# xplorer.net
KiCad netlist of a schematic drawn in EAGLE
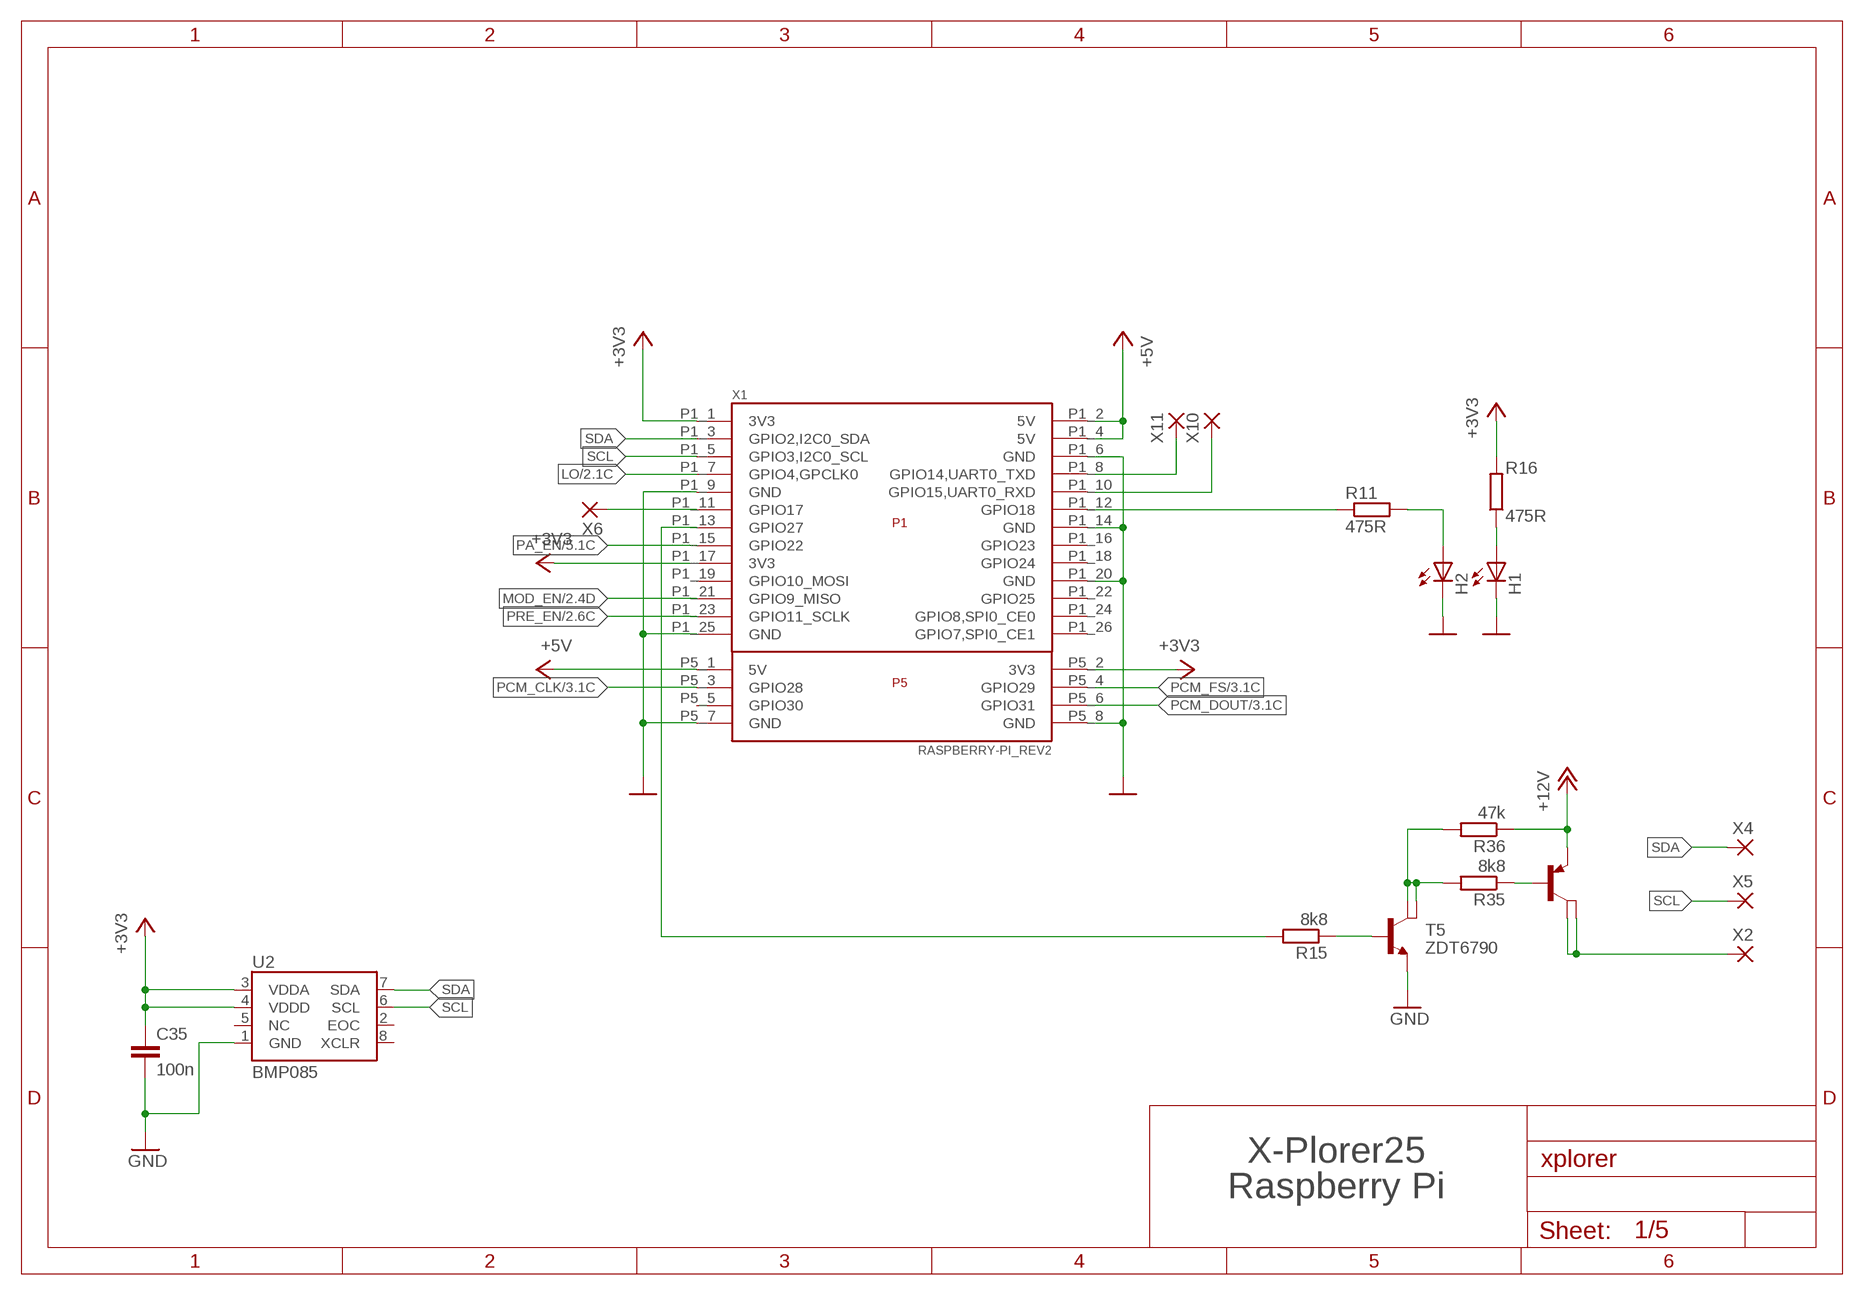
[diagram p0: schematic, sheet 1]
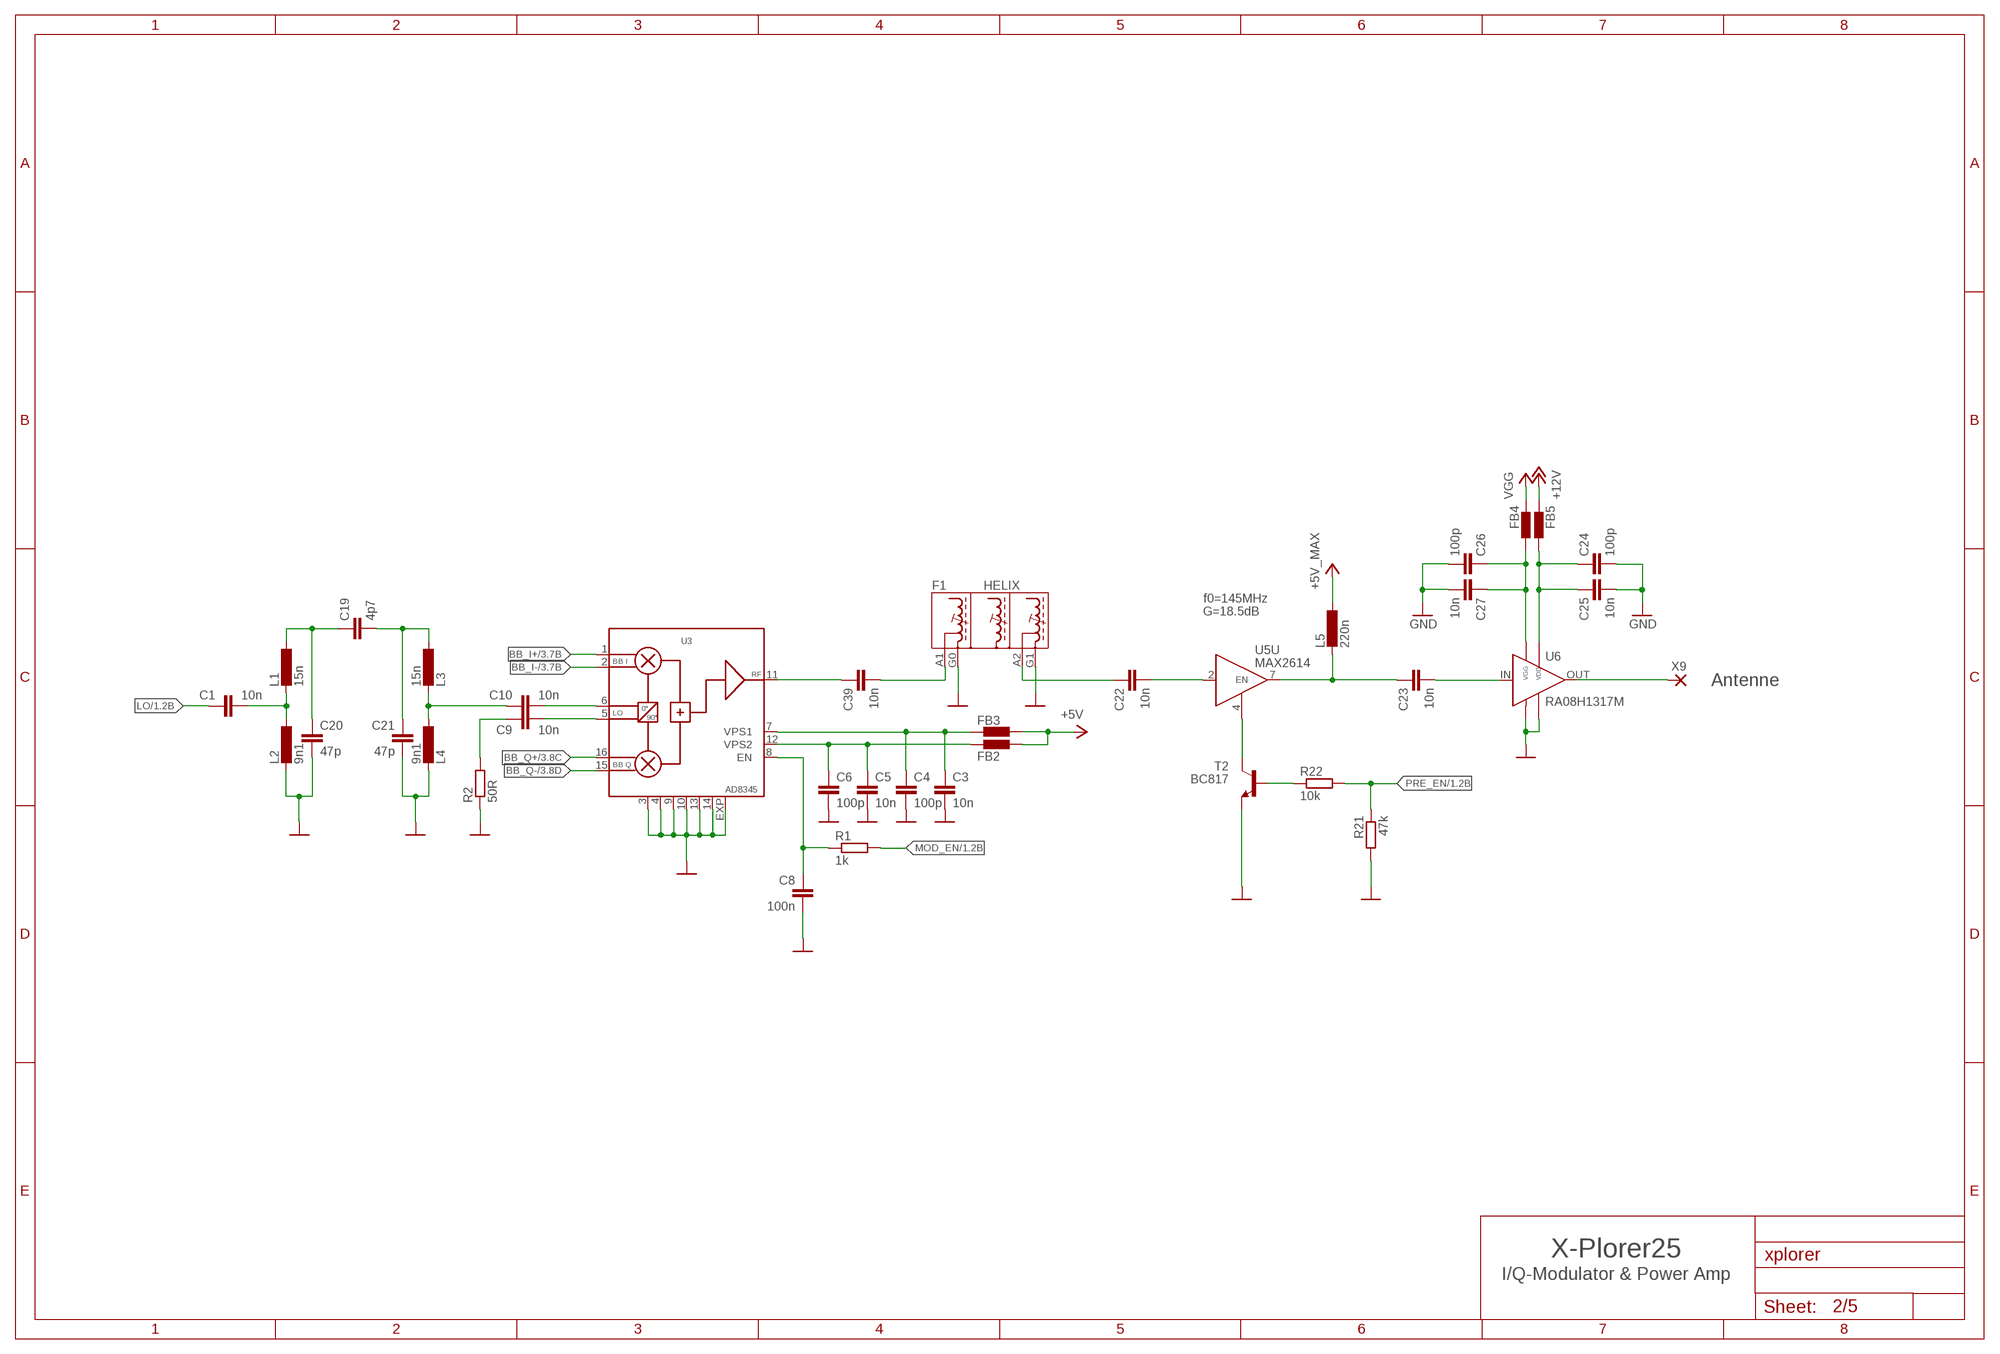
[diagram p1: schematic, sheet 2]
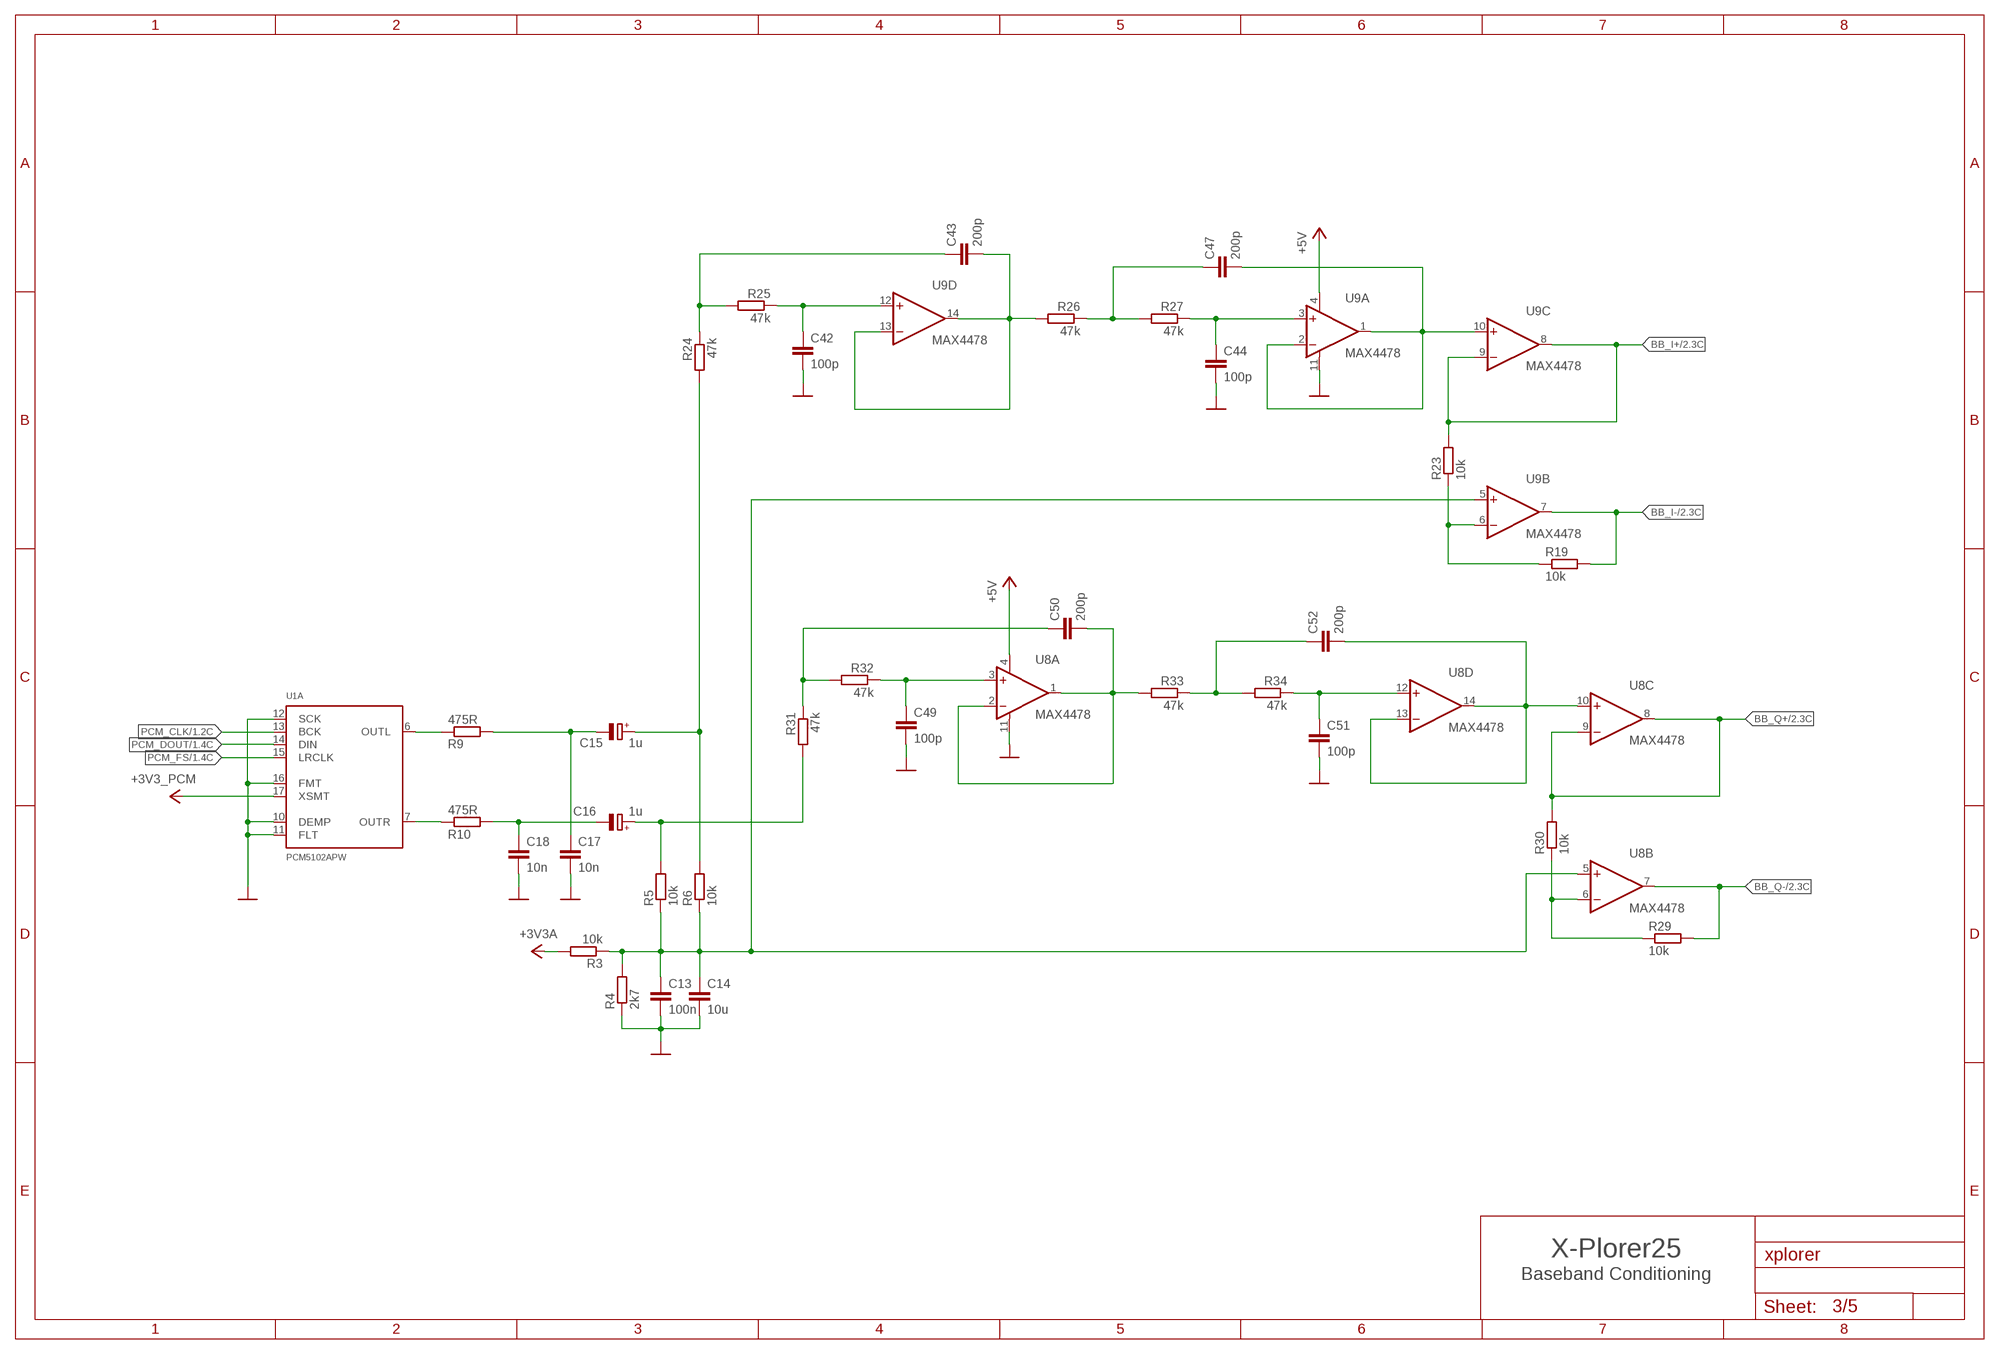
[diagram p2: schematic, sheet 3]
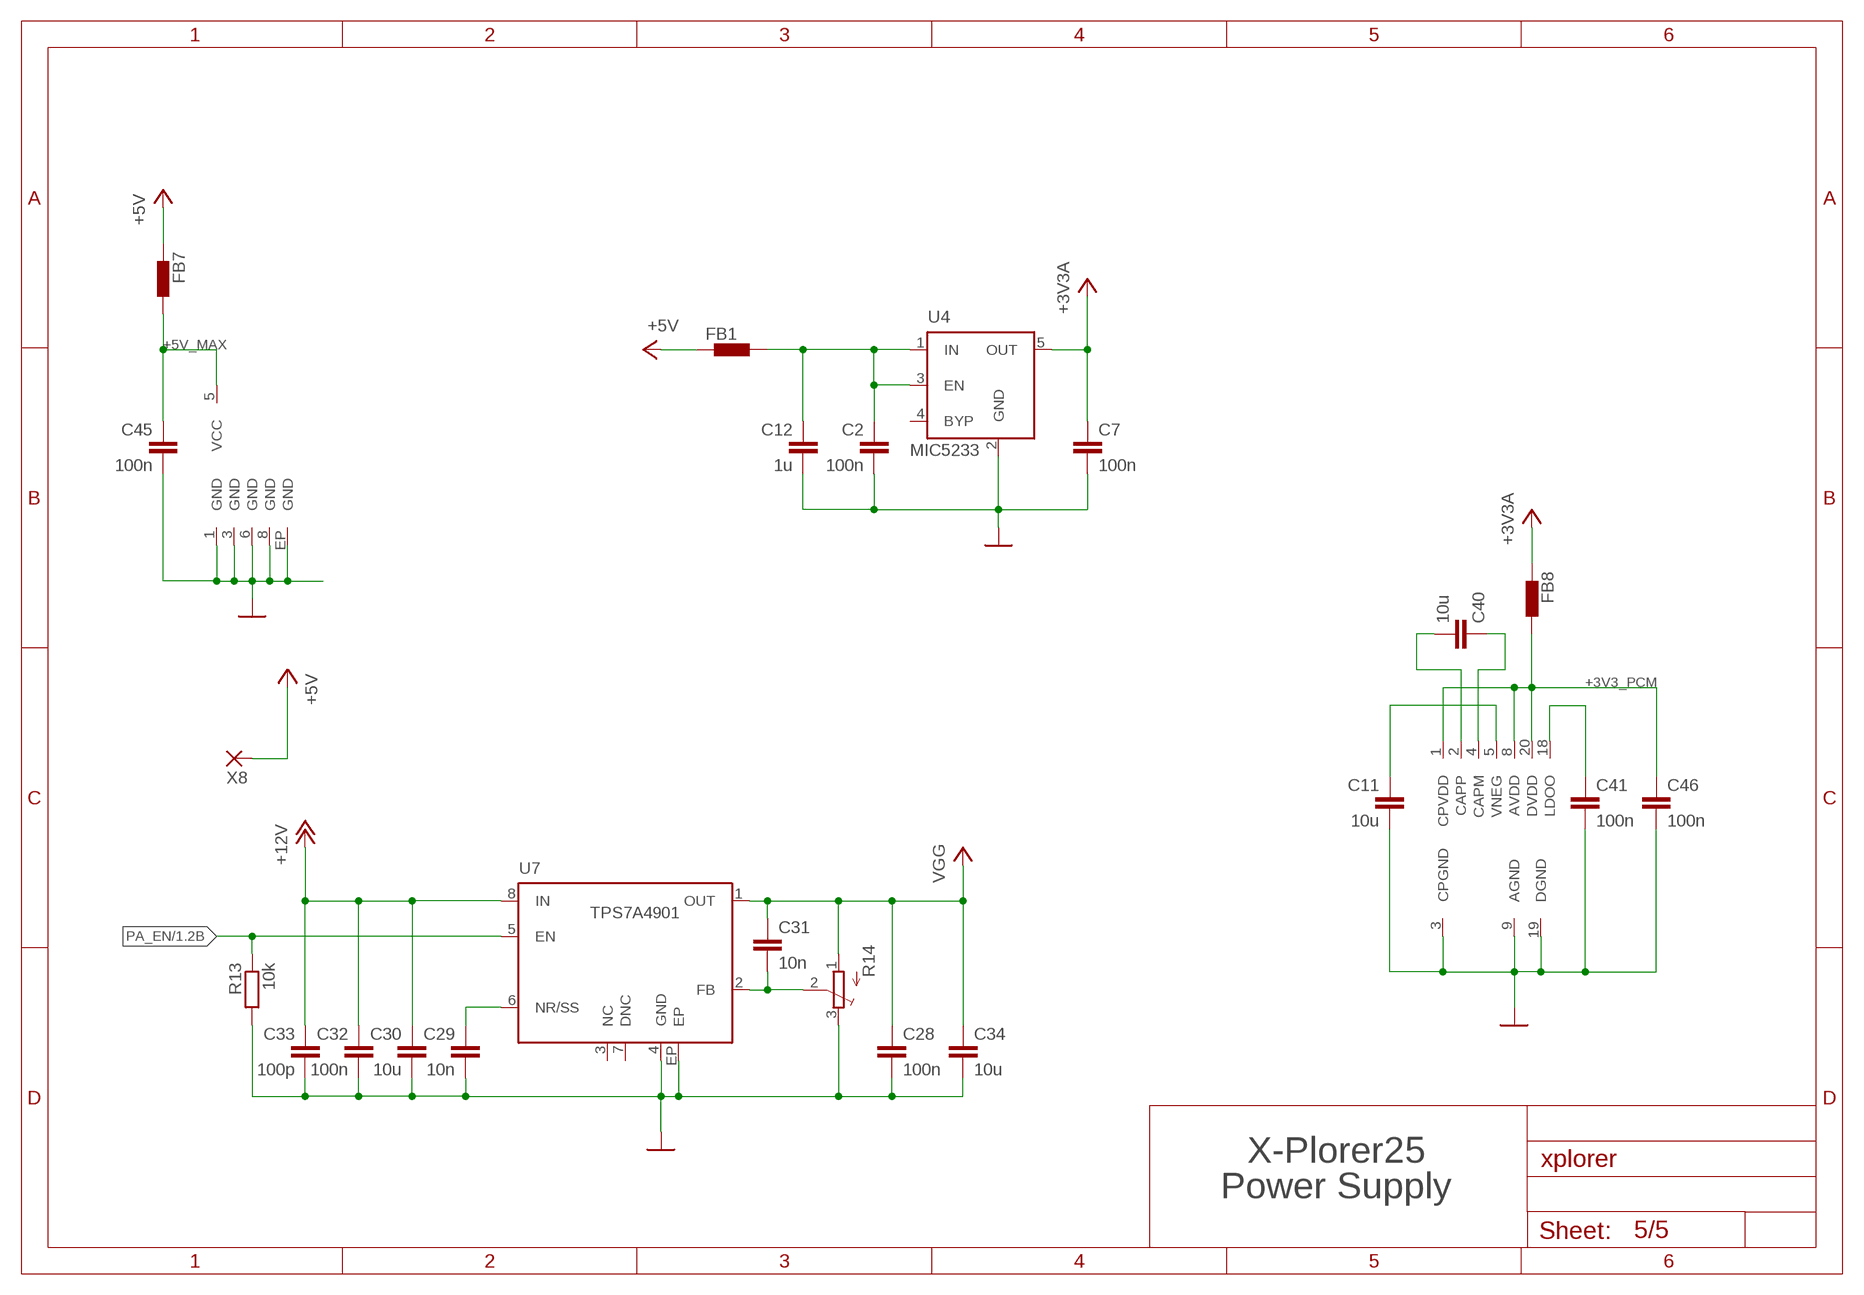
[diagram p3: schematic, sheet 5]

(export (version "E")
  (design (tool "Eeschema 10.0.6"))
  (components
    (comp (ref "C1")
      (value "10n")
      (footprint "eagle-import:C0603")
      (libsource (lib "eagle-import") (part "C-EUC0603"))
    )
    (comp (ref "C3")
      (value "10n")
      (footprint "eagle-import:C0603")
      (libsource (lib "eagle-import") (part "C-EUC0603"))
    )
    (comp (ref "C4")
      (value "100p")
      (footprint "eagle-import:C0603")
      (libsource (lib "eagle-import") (part "C-EUC0603"))
    )
    (comp (ref "C5")
      (value "10n")
      (footprint "eagle-import:C0603")
      (libsource (lib "eagle-import") (part "C-EUC0603"))
    )
    (comp (ref "C6")
      (value "100p")
      (footprint "eagle-import:C0603")
      (libsource (lib "eagle-import") (part "C-EUC0603"))
    )
    (comp (ref "C8")
      (value "100n")
      (footprint "eagle-import:C0603")
      (libsource (lib "eagle-import") (part "C-EUC0603"))
    )
    (comp (ref "C9")
      (value "10n")
      (footprint "eagle-import:C0603")
      (libsource (lib "eagle-import") (part "C-EUC0603"))
    )
    (comp (ref "C10")
      (value "10n")
      (footprint "eagle-import:C0603")
      (libsource (lib "eagle-import") (part "C-EUC0603"))
    )
    (comp (ref "C19")
      (value "4p7")
      (footprint "eagle-import:C0603")
      (libsource (lib "eagle-import") (part "C-EUC0603"))
    )
    (comp (ref "C20")
      (value "47p")
      (footprint "eagle-import:C1812")
      (libsource (lib "eagle-import") (part "C-EUC1812"))
    )
    (comp (ref "C21")
      (value "47p")
      (footprint "eagle-import:C1812")
      (libsource (lib "eagle-import") (part "C-EUC1812"))
    )
    (comp (ref "C22")
      (value "10n")
      (footprint "eagle-import:C0603")
      (libsource (lib "eagle-import") (part "C-EUC0603"))
    )
    (comp (ref "C23")
      (value "10n")
      (footprint "eagle-import:C0603")
      (libsource (lib "eagle-import") (part "C-EUC0603"))
    )
    (comp (ref "C24")
      (value "100p")
      (footprint "eagle-import:C0603")
      (libsource (lib "eagle-import") (part "C-EUC0603"))
    )
    (comp (ref "C25")
      (value "10n")
      (footprint "eagle-import:C0603")
      (libsource (lib "eagle-import") (part "C-EUC0603"))
    )
    (comp (ref "C26")
      (value "100p")
      (footprint "eagle-import:C0603")
      (libsource (lib "eagle-import") (part "C-EUC0603"))
    )
    (comp (ref "C27")
      (value "10n")
      (footprint "eagle-import:C0603")
      (libsource (lib "eagle-import") (part "C-EUC0603"))
    )
    (comp (ref "C39")
      (value "10n")
      (footprint "eagle-import:C0603")
      (libsource (lib "eagle-import") (part "C-EUC0603"))
    )
    (comp (ref "F1")
      (value "HELIX")
      (footprint "eagle-import:CBT13")
      (libsource (lib "eagle-import") (part "HELIX"))
    )
    (comp (ref "FB2")
      (value "BML15H")
      (footprint "eagle-import:R0603")
      (libsource (lib "eagle-import") (part "BML15H"))
    )
    (comp (ref "FB3")
      (value "BML15H")
      (footprint "eagle-import:R0603")
      (libsource (lib "eagle-import") (part "BML15H"))
    )
    (comp (ref "FB4")
      (value "BML15H")
      (footprint "eagle-import:R0603")
      (libsource (lib "eagle-import") (part "BML15H"))
    )
    (comp (ref "FB5")
      (value "BML15H")
      (footprint "eagle-import:R0603")
      (libsource (lib "eagle-import") (part "BML15H"))
    )
    (comp (ref "L1")
      (value "15n")
      (footprint "eagle-import:L2012C")
      (libsource (lib "eagle-import") (part "L-EUL2012C"))
    )
    (comp (ref "L2")
      (value "9n1")
      (footprint "eagle-import:L2012C")
      (libsource (lib "eagle-import") (part "L-EUL2012C"))
    )
    (comp (ref "L3")
      (value "15n")
      (footprint "eagle-import:L2012C")
      (libsource (lib "eagle-import") (part "L-EUL2012C"))
    )
    (comp (ref "L4")
      (value "9n1")
      (footprint "eagle-import:L2012C")
      (libsource (lib "eagle-import") (part "L-EUL2012C"))
    )
    (comp (ref "L5")
      (value "220n")
      (footprint "eagle-import:L2012C")
      (libsource (lib "eagle-import") (part "L-EUL2012C"))
    )
    (comp (ref "R1")
      (value "1k")
      (footprint "eagle-import:R0603")
      (libsource (lib "eagle-import") (part "R-EU_R0603"))
    )
    (comp (ref "R2")
      (value "50R")
      (footprint "eagle-import:R0603")
      (libsource (lib "eagle-import") (part "R-EU_R0603"))
    )
    (comp (ref "R21")
      (value "47k")
      (footprint "eagle-import:R0603")
      (libsource (lib "eagle-import") (part "R-EU_R0603"))
    )
    (comp (ref "R22")
      (value "10k")
      (footprint "eagle-import:R0603")
      (libsource (lib "eagle-import") (part "R-EU_R0603"))
    )
    (comp (ref "T2")
      (value "BC817")
      (footprint "eagle-import:SOT23-BEC")
      (libsource (lib "eagle-import") (part "BC817SMD-16LT1"))
    )
    (comp (ref "U3")
      (value "AD8345")
      (footprint "eagle-import:TSSOP16EXP")
      (libsource (lib "eagle-import") (part "AD8345"))
    )
    (comp (ref "U5")
      (value "MAX2614")
      (footprint "eagle-import:TDFN8-2X3MM")
      (libsource (lib "eagle-import") (part "MAX2615"))
    )
    (comp (ref "U6")
      (value "RA08H1317M")
      (footprint "eagle-import:RA08H1317M")
      (libsource (lib "eagle-import") (part "RA08H1317M"))
    )
    (comp (ref "X9")
      (value "SMD2")
      (footprint "eagle-import:SMD1,27-2,54")
      (libsource (lib "eagle-import") (part "SMD2"))
    )
    (comp (ref "C13")
      (value "100n")
      (footprint "eagle-import:C0603")
      (libsource (lib "eagle-import") (part "C-EUC0603"))
    )
    (comp (ref "C14")
      (value "10u")
      (footprint "eagle-import:C0603")
      (libsource (lib "eagle-import") (part "C-EUC0603"))
    )
    (comp (ref "C15")
      (value "1u")
      (footprint "eagle-import:CT3528")
      (libsource (lib "eagle-import") (part "CPOL-EUCT3528"))
    )
    (comp (ref "C16")
      (value "1u")
      (footprint "eagle-import:CT3528")
      (libsource (lib "eagle-import") (part "CPOL-EUCT3528"))
    )
    (comp (ref "C17")
      (value "10n")
      (footprint "eagle-import:C0603")
      (libsource (lib "eagle-import") (part "C-EUC0603"))
    )
    (comp (ref "C18")
      (value "10n")
      (footprint "eagle-import:C0603")
      (libsource (lib "eagle-import") (part "C-EUC0603"))
    )
    (comp (ref "C42")
      (value "100p")
      (footprint "eagle-import:C0603")
      (libsource (lib "eagle-import") (part "C-EUC0603"))
    )
    (comp (ref "C43")
      (value "200p")
      (footprint "eagle-import:C0805")
      (libsource (lib "eagle-import") (part "C-EUC0805"))
    )
    (comp (ref "C44")
      (value "100p")
      (footprint "eagle-import:C0603")
      (libsource (lib "eagle-import") (part "C-EUC0603"))
    )
    (comp (ref "C47")
      (value "200p")
      (footprint "eagle-import:C0805")
      (libsource (lib "eagle-import") (part "C-EUC0805"))
    )
    (comp (ref "C49")
      (value "100p")
      (footprint "eagle-import:C0603")
      (libsource (lib "eagle-import") (part "C-EUC0603"))
    )
    (comp (ref "C50")
      (value "200p")
      (footprint "eagle-import:C0805")
      (libsource (lib "eagle-import") (part "C-EUC0805"))
    )
    (comp (ref "C51")
      (value "100p")
      (footprint "eagle-import:C0603")
      (libsource (lib "eagle-import") (part "C-EUC0603"))
    )
    (comp (ref "C52")
      (value "200p")
      (footprint "eagle-import:C0805")
      (libsource (lib "eagle-import") (part "C-EUC0805"))
    )
    (comp (ref "R3")
      (value "10k")
      (footprint "eagle-import:R0603")
      (libsource (lib "eagle-import") (part "R-EU_R0603"))
    )
    (comp (ref "R4")
      (value "2k7")
      (footprint "eagle-import:R0603")
      (libsource (lib "eagle-import") (part "R-EU_R0603"))
    )
    (comp (ref "R5")
      (value "10k")
      (footprint "eagle-import:R0603")
      (libsource (lib "eagle-import") (part "R-EU_R0603"))
    )
    (comp (ref "R6")
      (value "10k")
      (footprint "eagle-import:R0603")
      (libsource (lib "eagle-import") (part "R-EU_R0603"))
    )
    (comp (ref "R9")
      (value "475R")
      (footprint "eagle-import:R0603")
      (libsource (lib "eagle-import") (part "R-EU_R0603"))
    )
    (comp (ref "R10")
      (value "475R")
      (footprint "eagle-import:R0603")
      (libsource (lib "eagle-import") (part "R-EU_R0603"))
    )
    (comp (ref "R19")
      (value "10k")
      (footprint "eagle-import:R0603")
      (libsource (lib "eagle-import") (part "R-EU_R0603"))
    )
    (comp (ref "R23")
      (value "10k")
      (footprint "eagle-import:R0603")
      (libsource (lib "eagle-import") (part "R-EU_R0603"))
    )
    (comp (ref "R24")
      (value "47k")
      (footprint "eagle-import:R0603")
      (libsource (lib "eagle-import") (part "R-EU_R0603"))
    )
    (comp (ref "R25")
      (value "47k")
      (footprint "eagle-import:R0603")
      (libsource (lib "eagle-import") (part "R-EU_R0603"))
    )
    (comp (ref "R26")
      (value "47k")
      (footprint "eagle-import:R0603")
      (libsource (lib "eagle-import") (part "R-EU_R0603"))
    )
    (comp (ref "R27")
      (value "47k")
      (footprint "eagle-import:R0603")
      (libsource (lib "eagle-import") (part "R-EU_R0603"))
    )
    (comp (ref "R29")
      (value "10k")
      (footprint "eagle-import:R0603")
      (libsource (lib "eagle-import") (part "R-EU_R0603"))
    )
    (comp (ref "R30")
      (value "10k")
      (footprint "eagle-import:R0603")
      (libsource (lib "eagle-import") (part "R-EU_R0603"))
    )
    (comp (ref "R31")
      (value "47k")
      (footprint "eagle-import:R0603")
      (libsource (lib "eagle-import") (part "R-EU_R0603"))
    )
    (comp (ref "R32")
      (value "47k")
      (footprint "eagle-import:R0603")
      (libsource (lib "eagle-import") (part "R-EU_R0603"))
    )
    (comp (ref "R33")
      (value "47k")
      (footprint "eagle-import:R0603")
      (libsource (lib "eagle-import") (part "R-EU_R0603"))
    )
    (comp (ref "R34")
      (value "47k")
      (footprint "eagle-import:R0603")
      (libsource (lib "eagle-import") (part "R-EU_R0603"))
    )
    (comp (ref "U1")
      (value "PCM5102APW")
      (footprint "eagle-import:PW_R-PDSO-G20")
      (libsource (lib "eagle-import") (part "PCM5102APW"))
    )
    (comp (ref "U8")
      (value "MAX4478")
      (footprint "eagle-import:SO14")
      (fields
        (field (name "MF") "TEXAS INSTRUMENTS")
        (field (name "MPN") "OPA4132UA")
        (field (name "MF_1") "TEXAS INSTRUMENTS")
        (field (name "MPN_1") "OPA4132UA")
        (field (name "OC_FARNELL") "1212302")
        (field (name "OC_NEWARK") "80K6028")
      )
      (libsource (lib "eagle-import") (part "OPA4132U"))
    )
    (comp (ref "U9")
      (value "MAX4478")
      (footprint "eagle-import:SO14")
      (fields (field (name "MF") "TEXAS INSTRUMENTS") (field (name "MPN") "OPA4132UA"))
      (libsource (lib "eagle-import") (part "OPA4132U"))
    )
    (comp (ref "C2")
      (value "100n")
      (footprint "eagle-import:C0603")
      (libsource (lib "eagle-import") (part "C-EUC0603"))
    )
    (comp (ref "C7")
      (value "100n")
      (footprint "eagle-import:C0603")
      (libsource (lib "eagle-import") (part "C-EUC0603"))
    )
    (comp (ref "C11")
      (value "10u")
      (footprint "eagle-import:C0603")
      (libsource (lib "eagle-import") (part "C-EUC0603"))
    )
    (comp (ref "C12")
      (value "1u")
      (footprint "eagle-import:C0603")
      (libsource (lib "eagle-import") (part "C-EUC0603"))
    )
    (comp (ref "C28")
      (value "100n")
      (footprint "eagle-import:C0603")
      (libsource (lib "eagle-import") (part "C-EUC0603"))
    )
    (comp (ref "C29")
      (value "10n")
      (footprint "eagle-import:C0603K")
      (libsource (lib "eagle-import") (part "C-EUC0603K"))
    )
    (comp (ref "C30")
      (value "10u")
      (footprint "eagle-import:C0805")
      (libsource (lib "eagle-import") (part "C-EUC0805"))
    )
    (comp (ref "C31")
      (value "10n")
      (footprint "eagle-import:C0603")
      (libsource (lib "eagle-import") (part "C-EUC0603"))
    )
    (comp (ref "C32")
      (value "100n")
      (footprint "eagle-import:C0603")
      (libsource (lib "eagle-import") (part "C-EUC0603"))
    )
    (comp (ref "C33")
      (value "100p")
      (footprint "eagle-import:C0603")
      (libsource (lib "eagle-import") (part "C-EUC0603"))
    )
    (comp (ref "C34")
      (value "10u")
      (footprint "eagle-import:C0805")
      (libsource (lib "eagle-import") (part "C-EUC0805"))
    )
    (comp (ref "C40")
      (value "10u")
      (footprint "eagle-import:C0603")
      (libsource (lib "eagle-import") (part "C-EUC0603"))
    )
    (comp (ref "C41")
      (value "100n")
      (footprint "eagle-import:C0603")
      (libsource (lib "eagle-import") (part "C-EUC0603"))
    )
    (comp (ref "C45")
      (value "100n")
      (footprint "eagle-import:C0603")
      (libsource (lib "eagle-import") (part "C-EUC0603"))
    )
    (comp (ref "C46")
      (value "100n")
      (footprint "eagle-import:C0603")
      (libsource (lib "eagle-import") (part "C-EUC0603"))
    )
    (comp (ref "FB1")
      (value "BML15H")
      (footprint "eagle-import:R0603")
      (libsource (lib "eagle-import") (part "BML15H"))
    )
    (comp (ref "FB7")
      (value "BML15H")
      (footprint "eagle-import:R0603")
      (libsource (lib "eagle-import") (part "BML15H"))
    )
    (comp (ref "FB8")
      (value "BML15H")
      (footprint "eagle-import:R0603")
      (libsource (lib "eagle-import") (part "BML15H"))
    )
    (comp (ref "R13")
      (value "10k")
      (footprint "eagle-import:R0603")
      (libsource (lib "eagle-import") (part "R-EU_R0603"))
    )
    (comp (ref "R14")
      (value "TRIM_EU-SM-42/43X")
      (footprint "eagle-import:SM-42_43X")
      (libsource (lib "eagle-import") (part "TRIM_EU-SM-42/43X"))
    )
    (comp (ref "U4")
      (value "MIC5233")
      (footprint "eagle-import:SOT23-5")
      (libsource (lib "eagle-import") (part "MIC5219XX"))
    )
    (comp (ref "U7")
      (value "TPS7A4901")
      (footprint "eagle-import:PW_R-PDSO-G08")
      (libsource (lib "eagle-import") (part "TPS7A4901"))
    )
    (comp (ref "X8")
      (value "SMD2")
      (footprint "eagle-import:SMD1,27-2,54")
      (libsource (lib "eagle-import") (part "SMD2"))
    )
    (comp (ref "C35")
      (value "100n")
      (footprint "eagle-import:0603")
      (libsource (lib "eagle-import") (part "C-0603"))
    )
    (comp (ref "H1")
      (value "LEDCHIPLED_0603")
      (footprint "eagle-import:CHIPLED_0603")
      (libsource (lib "eagle-import") (part "LEDCHIPLED_0603"))
    )
    (comp (ref "H2")
      (value "LEDCHIPLED_0603")
      (footprint "eagle-import:CHIPLED_0603")
      (libsource (lib "eagle-import") (part "LEDCHIPLED_0603"))
    )
    (comp (ref "R11")
      (value "475R")
      (footprint "eagle-import:R0402")
      (libsource (lib "eagle-import") (part "R-EU_R0402"))
    )
    (comp (ref "R15")
      (value "8k8")
      (footprint "eagle-import:R0603")
      (libsource (lib "eagle-import") (part "R-EU_R0603"))
    )
    (comp (ref "R16")
      (value "475R")
      (footprint "eagle-import:R0402")
      (libsource (lib "eagle-import") (part "R-EU_R0402"))
    )
    (comp (ref "R35")
      (value "8k8")
      (footprint "eagle-import:R0603")
      (libsource (lib "eagle-import") (part "R-EU_R0603"))
    )
    (comp (ref "R36")
      (value "47k")
      (footprint "eagle-import:R0603")
      (libsource (lib "eagle-import") (part "R-EU_R0603"))
    )
    (comp (ref "T5")
      (value "ZDT6790")
      (footprint "eagle-import:SOT223-8")
      (libsource (lib "eagle-import") (part "ZDT6790"))
    )
    (comp (ref "U2")
      (value "BMP085")
      (footprint "eagle-import:BMP085")
      (libsource (lib "eagle-import") (part "BMP085"))
    )
    (comp (ref "X1")
      (value "RASPBERRY-PI_REV2")
      (footprint "eagle-import:RASPBERRY-PI_REV2")
      (libsource (lib "eagle-import") (part "RASPBERRY-PI_REV2"))
    )
    (comp (ref "X2")
      (value "SMD2")
      (footprint "eagle-import:SMD1,27-2,54")
      (libsource (lib "eagle-import") (part "SMD2"))
    )
    (comp (ref "X4")
      (value "SMD2")
      (footprint "eagle-import:SMD1,27-2,54")
      (libsource (lib "eagle-import") (part "SMD2"))
    )
    (comp (ref "X5")
      (value "SMD2")
      (footprint "eagle-import:SMD1,27-2,54")
      (libsource (lib "eagle-import") (part "SMD2"))
    )
    (comp (ref "X6")
      (value "SMD2")
      (footprint "eagle-import:SMD1,27-2,54")
      (libsource (lib "eagle-import") (part "SMD2"))
    )
    (comp (ref "X10")
      (value "SMD2")
      (footprint "eagle-import:SMD1,27-2,54")
      (libsource (lib "eagle-import") (part "SMD2"))
    )
    (comp (ref "X11")
      (value "SMD2")
      (footprint "eagle-import:SMD1,27-2,54")
      (libsource (lib "eagle-import") (part "SMD2"))
    )
  )
  (nets
    (net (code "1") (name "+3V3") (class "Default")
      (node (ref "C35") (pin "1") (pinfunction "1_1") (pintype "passive"))
      (node (ref "R16") (pin "2") (pinfunction "2_2") (pintype "passive"))
      (node (ref "U2") (pin "3") (pinfunction "VDDA_3") (pintype "power_in"))
      (node (ref "U2") (pin "4") (pinfunction "VDDD_4") (pintype "power_in"))
      (node (ref "X1") (pin "P1_1") (pinfunction "3V3_P1_1") (pintype "bidirectional"))
      (node (ref "X1") (pin "P1_17") (pinfunction "3V3_P1_17") (pintype "bidirectional"))
      (node (ref "X1") (pin "P5_2") (pinfunction "3V3_P5_2") (pintype "bidirectional"))
    )
    (net (code "2") (name "+3V3A") (class "Default")
      (node (ref "C7") (pin "1") (pinfunction "1_1") (pintype "passive"))
      (node (ref "FB8") (pin "1") (pinfunction "1_1") (pintype "passive"))
      (node (ref "R3") (pin "2") (pinfunction "2_2") (pintype "passive"))
      (node (ref "U4") (pin "5") (pinfunction "OUT_5") (pintype "output"))
    )
    (net (code "3") (name "+3V3_PCM") (class "Default")
      (node (ref "C46") (pin "1") (pinfunction "1_1") (pintype "passive"))
      (node (ref "FB8") (pin "2") (pinfunction "2_2") (pintype "passive"))
      (node (ref "U1") (pin "1") (pinfunction "CPVDD_1") (pintype "power_in"))
      (node (ref "U1") (pin "17") (pinfunction "XSMT_17") (pintype "input"))
      (node (ref "U1") (pin "20") (pinfunction "DVDD_20") (pintype "power_in"))
      (node (ref "U1") (pin "8") (pinfunction "AVDD_8") (pintype "power_in"))
    )
    (net (code "4") (name "+5V") (class "Default")
      (node (ref "FB1") (pin "1") (pinfunction "1_1") (pintype "passive"))
      (node (ref "FB2") (pin "2") (pinfunction "2_2") (pintype "passive"))
      (node (ref "FB3") (pin "2") (pinfunction "2_2") (pintype "passive"))
      (node (ref "FB7") (pin "1") (pinfunction "1_1") (pintype "passive"))
      (node (ref "U8") (pin "4") (pinfunction "V+_4") (pintype "power_in"))
      (node (ref "U9") (pin "4") (pinfunction "V+_4") (pintype "power_in"))
      (node (ref "X1") (pin "P1_2") (pinfunction "5V_P1_2") (pintype "bidirectional"))
      (node (ref "X1") (pin "P1_4") (pinfunction "5V_P1_4") (pintype "bidirectional"))
      (node (ref "X1") (pin "P5_1") (pinfunction "5V_P5_1") (pintype "bidirectional"))
      (node (ref "X8") (pin "1") (pinfunction "P_1") (pintype "passive"))
    )
    (net (code "5") (name "+5V_MAX") (class "Default")
      (node (ref "C45") (pin "1") (pinfunction "1_1") (pintype "passive"))
      (node (ref "FB7") (pin "2") (pinfunction "2_2") (pintype "passive"))
      (node (ref "L5") (pin "1") (pinfunction "1_1") (pintype "passive"))
      (node (ref "U5") (pin "5") (pinfunction "VCC_5") (pintype "power_in"))
    )
    (net (code "6") (name "+12V") (class "Default")
      (node (ref "C30") (pin "1") (pinfunction "1_1") (pintype "passive"))
      (node (ref "C32") (pin "1") (pinfunction "1_1") (pintype "passive"))
      (node (ref "C33") (pin "1") (pinfunction "1_1") (pintype "passive"))
      (node (ref "FB5") (pin "1") (pinfunction "1_1") (pintype "passive"))
      (node (ref "R36") (pin "1") (pinfunction "1_1") (pintype "passive"))
      (node (ref "T5") (pin "5") (pinfunction "E_5") (pintype "passive"))
      (node (ref "U7") (pin "8") (pinfunction "IN_8") (pintype "input"))
    )
    (net (code "7") (name "BB_I+") (class "Default")
      (node (ref "R23") (pin "2") (pinfunction "2_2") (pintype "passive"))
      (node (ref "U3") (pin "1") (pinfunction "BB_I_1") (pintype "input"))
      (node (ref "U9") (pin "8") (pinfunction "OUT_8") (pintype "output"))
      (node (ref "U9") (pin "9") (pinfunction "-IN_9") (pintype "input"))
    )
    (net (code "8") (name "BB_I-") (class "Default")
      (node (ref "R19") (pin "2") (pinfunction "2_2") (pintype "passive"))
      (node (ref "U3") (pin "2") (pinfunction "~{BB_I}_2") (pintype "input"))
      (node (ref "U9") (pin "7") (pinfunction "OUT_7") (pintype "output"))
    )
    (net (code "9") (name "BB_Q+") (class "Default")
      (node (ref "R30") (pin "2") (pinfunction "2_2") (pintype "passive"))
      (node (ref "U3") (pin "16") (pinfunction "BB_Q_16") (pintype "input"))
      (node (ref "U8") (pin "8") (pinfunction "OUT_8") (pintype "output"))
      (node (ref "U8") (pin "9") (pinfunction "-IN_9") (pintype "input"))
    )
    (net (code "10") (name "BB_Q-") (class "Default")
      (node (ref "R29") (pin "2") (pinfunction "2_2") (pintype "passive"))
      (node (ref "U3") (pin "15") (pinfunction "~{BB_Q}_15") (pintype "input"))
      (node (ref "U8") (pin "7") (pinfunction "OUT_7") (pintype "output"))
    )
    (net (code "11") (name "GND") (class "Default")
      (node (ref "C11") (pin "2") (pinfunction "2_2") (pintype "passive"))
      (node (ref "C12") (pin "2") (pinfunction "2_2") (pintype "passive"))
      (node (ref "C13") (pin "2") (pinfunction "2_2") (pintype "passive"))
      (node (ref "C14") (pin "2") (pinfunction "2_2") (pintype "passive"))
      (node (ref "C17") (pin "2") (pinfunction "2_2") (pintype "passive"))
      (node (ref "C18") (pin "2") (pinfunction "2_2") (pintype "passive"))
      (node (ref "C2") (pin "2") (pinfunction "2_2") (pintype "passive"))
      (node (ref "C20") (pin "2") (pinfunction "2_2") (pintype "passive"))
      (node (ref "C21") (pin "2") (pinfunction "2_2") (pintype "passive"))
      (node (ref "C24") (pin "2") (pinfunction "2_2") (pintype "passive"))
      (node (ref "C25") (pin "2") (pinfunction "2_2") (pintype "passive"))
      (node (ref "C26") (pin "2") (pinfunction "2_2") (pintype "passive"))
      (node (ref "C27") (pin "2") (pinfunction "2_2") (pintype "passive"))
      (node (ref "C28") (pin "2") (pinfunction "2_2") (pintype "passive"))
      (node (ref "C29") (pin "2") (pinfunction "2_2") (pintype "passive"))
      (node (ref "C3") (pin "2") (pinfunction "2_2") (pintype "passive"))
      (node (ref "C30") (pin "2") (pinfunction "2_2") (pintype "passive"))
      (node (ref "C32") (pin "2") (pinfunction "2_2") (pintype "passive"))
      (node (ref "C33") (pin "2") (pinfunction "2_2") (pintype "passive"))
      (node (ref "C34") (pin "2") (pinfunction "2_2") (pintype "passive"))
      (node (ref "C35") (pin "2") (pinfunction "2_2") (pintype "passive"))
      (node (ref "C4") (pin "2") (pinfunction "2_2") (pintype "passive"))
      (node (ref "C41") (pin "2") (pinfunction "2_2") (pintype "passive"))
      (node (ref "C42") (pin "2") (pinfunction "2_2") (pintype "passive"))
      (node (ref "C44") (pin "2") (pinfunction "2_2") (pintype "passive"))
      (node (ref "C45") (pin "2") (pinfunction "2_2") (pintype "passive"))
      (node (ref "C46") (pin "2") (pinfunction "2_2") (pintype "passive"))
      (node (ref "C49") (pin "2") (pinfunction "2_2") (pintype "passive"))
      (node (ref "C5") (pin "2") (pinfunction "2_2") (pintype "passive"))
      (node (ref "C51") (pin "2") (pinfunction "2_2") (pintype "passive"))
      (node (ref "C6") (pin "2") (pinfunction "2_2") (pintype "passive"))
      (node (ref "C7") (pin "2") (pinfunction "2_2") (pintype "passive"))
      (node (ref "C8") (pin "2") (pinfunction "2_2") (pintype "passive"))
      (node (ref "F1") (pin "G0") (pinfunction "GND_G0") (pintype "passive"))
      (node (ref "F1") (pin "G1") (pinfunction "GND_G1") (pintype "passive"))
      (node (ref "H1") (pin "C") (pinfunction "C_C") (pintype "passive"))
      (node (ref "H2") (pin "C") (pinfunction "C_C") (pintype "passive"))
      (node (ref "L2") (pin "2") (pinfunction "2_2") (pintype "passive"))
      (node (ref "L4") (pin "2") (pinfunction "2_2") (pintype "passive"))
      (node (ref "R13") (pin "2") (pinfunction "2_2") (pintype "passive"))
      (node (ref "R14") (pin "3") (pinfunction "E_3") (pintype "passive"))
      (node (ref "R2") (pin "1") (pinfunction "1_1") (pintype "passive"))
      (node (ref "R21") (pin "2") (pinfunction "2_2") (pintype "passive"))
      (node (ref "R4") (pin "1") (pinfunction "1_1") (pintype "passive"))
      (node (ref "T2") (pin "E") (pinfunction "E_E") (pintype "passive"))
      (node (ref "T5") (pin "7") (pinfunction "E_7") (pintype "passive"))
      (node (ref "U1") (pin "10") (pinfunction "DEMP_10") (pintype "input"))
      (node (ref "U1") (pin "11") (pinfunction "FLT_11") (pintype "input"))
      (node (ref "U1") (pin "12") (pinfunction "SCK_12") (pintype "input"))
      (node (ref "U1") (pin "16") (pinfunction "FMT_16") (pintype "input"))
      (node (ref "U1") (pin "19") (pinfunction "DGND_19") (pintype "power_in"))
      (node (ref "U1") (pin "3") (pinfunction "CPGND_3") (pintype "power_in"))
      (node (ref "U1") (pin "9") (pinfunction "AGND_9") (pintype "power_in"))
      (node (ref "U2") (pin "1") (pinfunction "GND_1") (pintype "power_in"))
      (node (ref "U3") (pin "10") (pinfunction "GND_10") (pintype "power_in"))
      (node (ref "U3") (pin "13") (pinfunction "GND_13") (pintype "power_in"))
      (node (ref "U3") (pin "14") (pinfunction "GND_14") (pintype "power_in"))
      (node (ref "U3") (pin "3") (pinfunction "GND_3") (pintype "power_in"))
      (node (ref "U3") (pin "4") (pinfunction "GND_4") (pintype "power_in"))
      (node (ref "U3") (pin "9") (pinfunction "GND_9") (pintype "power_in"))
      (node (ref "U3") (pin "EXP") (pinfunction "GND_EXP") (pintype "power_in"))
      (node (ref "U4") (pin "2") (pinfunction "GND_2") (pintype "power_in"))
      (node (ref "U5") (pin "1") (pinfunction "GND_1") (pintype "power_in"))
      (node (ref "U5") (pin "3") (pinfunction "GND_3") (pintype "power_in"))
      (node (ref "U5") (pin "6") (pinfunction "GND_6") (pintype "power_in"))
      (node (ref "U5") (pin "8") (pinfunction "GND_8") (pintype "power_in"))
      (node (ref "U5") (pin "EP") (pinfunction "GND_EP") (pintype "power_in"))
      (node (ref "U6") (pin "G1") (pinfunction "GND_G1") (pintype "power_in"))
      (node (ref "U6") (pin "G2") (pinfunction "GND_G2") (pintype "power_in"))
      (node (ref "U7") (pin "4") (pinfunction "GND_4") (pintype "power_in"))
      (node (ref "U7") (pin "EP") (pinfunction "EP_EP") (pintype "passive"))
      (node (ref "U8") (pin "11") (pinfunction "V-_11") (pintype "power_in"))
      (node (ref "U9") (pin "11") (pinfunction "V-_11") (pintype "power_in"))
      (node (ref "X1") (pin "P1_14") (pinfunction "GND_P1_14") (pintype "bidirectional"))
      (node (ref "X1") (pin "P1_20") (pinfunction "GND_P1_20") (pintype "bidirectional"))
      (node (ref "X1") (pin "P1_25") (pinfunction "GND_P1_25") (pintype "bidirectional"))
      (node (ref "X1") (pin "P1_6") (pinfunction "GND_P1_6") (pintype "bidirectional"))
      (node (ref "X1") (pin "P1_9") (pinfunction "GND_P1_9") (pintype "bidirectional"))
      (node (ref "X1") (pin "P5_7") (pinfunction "GND_P5_7") (pintype "bidirectional"))
      (node (ref "X1") (pin "P5_8") (pinfunction "GND_P5_8") (pintype "bidirectional"))
    )
    (net (code "12") (name "LO") (class "Default")
      (node (ref "C1") (pin "1") (pinfunction "1_1") (pintype "passive"))
      (node (ref "X1") (pin "P1_7") (pinfunction "GPIO4,GPCLK0_P1_7") (pintype "bidirectional"))
    )
    (net (code "13") (name "MOD_EN") (class "Default")
      (node (ref "R1") (pin "2") (pinfunction "2_2") (pintype "passive"))
      (node (ref "X1") (pin "P1_21") (pinfunction "GPIO9_MISO_P1_21") (pintype "bidirectional"))
    )
    (net (code "14") (name "Net-(C1-Pad2)") (class "Default")
      (node (ref "C1") (pin "2") (pinfunction "2_2") (pintype "passive"))
      (node (ref "L1") (pin "2") (pinfunction "2_2") (pintype "passive"))
      (node (ref "L2") (pin "1") (pinfunction "1_1") (pintype "passive"))
    )
    (net (code "15") (name "Net-(C9-Pad1)") (class "Default")
      (node (ref "C9") (pin "1") (pinfunction "1_1") (pintype "passive"))
      (node (ref "R2") (pin "2") (pinfunction "2_2") (pintype "passive"))
    )
    (net (code "16") (name "Net-(C10-Pad1)") (class "Default")
      (node (ref "C10") (pin "1") (pinfunction "1_1") (pintype "passive"))
      (node (ref "L3") (pin "2") (pinfunction "2_2") (pintype "passive"))
      (node (ref "L4") (pin "1") (pinfunction "1_1") (pintype "passive"))
    )
    (net (code "17") (name "Net-(C15-Pad+)") (class "Default")
      (node (ref "C15") (pin "+") (pinfunction "+_+") (pintype "passive"))
      (node (ref "R24") (pin "2") (pinfunction "2_2") (pintype "passive"))
      (node (ref "R6") (pin "2") (pinfunction "2_2") (pintype "passive"))
    )
    (net (code "18") (name "Net-(C15-Pad-)") (class "Default")
      (node (ref "C15") (pin "-") (pinfunction "-_-") (pintype "passive"))
      (node (ref "C17") (pin "1") (pinfunction "1_1") (pintype "passive"))
      (node (ref "R9") (pin "2") (pinfunction "2_2") (pintype "passive"))
    )
    (net (code "19") (name "Net-(C16-Pad+)") (class "Default")
      (node (ref "C16") (pin "+") (pinfunction "+_+") (pintype "passive"))
      (node (ref "R31") (pin "2") (pinfunction "2_2") (pintype "passive"))
      (node (ref "R5") (pin "2") (pinfunction "2_2") (pintype "passive"))
    )
    (net (code "20") (name "Net-(C16-Pad-)") (class "Default")
      (node (ref "C16") (pin "-") (pinfunction "-_-") (pintype "passive"))
      (node (ref "C18") (pin "1") (pinfunction "1_1") (pintype "passive"))
      (node (ref "R10") (pin "2") (pinfunction "2_2") (pintype "passive"))
    )
    (net (code "21") (name "Net-(C19-Pad1)") (class "Default")
      (node (ref "C19") (pin "1") (pinfunction "1_1") (pintype "passive"))
      (node (ref "C20") (pin "1") (pinfunction "1_1") (pintype "passive"))
      (node (ref "L1") (pin "1") (pinfunction "1_1") (pintype "passive"))
    )
    (net (code "22") (name "Net-(C19-Pad2)") (class "Default")
      (node (ref "C19") (pin "2") (pinfunction "2_2") (pintype "passive"))
      (node (ref "C21") (pin "1") (pinfunction "1_1") (pintype "passive"))
      (node (ref "L3") (pin "1") (pinfunction "1_1") (pintype "passive"))
    )
    (net (code "23") (name "Net-(C22-Pad1)") (class "Default")
      (node (ref "C22") (pin "1") (pinfunction "1_1") (pintype "passive"))
      (node (ref "F1") (pin "A2") (pinfunction "A2_A2") (pintype "passive"))
    )
    (net (code "24") (name "Net-(C23-Pad2)") (class "Default")
      (node (ref "C23") (pin "2") (pinfunction "2_2") (pintype "passive"))
      (node (ref "U6") (pin "IN") (pinfunction "IN_IN") (pintype "input"))
    )
    (net (code "25") (name "Net-(C24-Pad1)") (class "Default")
      (node (ref "C24") (pin "1") (pinfunction "1_1") (pintype "passive"))
      (node (ref "C25") (pin "1") (pinfunction "1_1") (pintype "passive"))
      (node (ref "FB5") (pin "2") (pinfunction "2_2") (pintype "passive"))
      (node (ref "U6") (pin "VDD") (pinfunction "VDD_VDD") (pintype "power_in"))
    )
    (net (code "26") (name "Net-(C26-Pad1)") (class "Default")
      (node (ref "C26") (pin "1") (pinfunction "1_1") (pintype "passive"))
      (node (ref "C27") (pin "1") (pinfunction "1_1") (pintype "passive"))
      (node (ref "FB4") (pin "2") (pinfunction "2_2") (pintype "passive"))
      (node (ref "U6") (pin "VGG") (pinfunction "VGG_VGG") (pintype "power_in"))
    )
    (net (code "27") (name "Net-(C39-Pad2)") (class "Default")
      (node (ref "C39") (pin "2") (pinfunction "2_2") (pintype "passive"))
      (node (ref "F1") (pin "A1") (pinfunction "A1_A1") (pintype "passive"))
    )
    (net (code "28") (name "Net-(C43-Pad1)") (class "Default")
      (node (ref "C43") (pin "1") (pinfunction "1_1") (pintype "passive"))
      (node (ref "R24") (pin "1") (pinfunction "1_1") (pintype "passive"))
      (node (ref "R25") (pin "2") (pinfunction "2_2") (pintype "passive"))
    )
    (net (code "29") (name "Net-(C47-Pad1)") (class "Default")
      (node (ref "C47") (pin "1") (pinfunction "1_1") (pintype "passive"))
      (node (ref "R26") (pin "1") (pinfunction "1_1") (pintype "passive"))
      (node (ref "R27") (pin "2") (pinfunction "2_2") (pintype "passive"))
    )
    (net (code "30") (name "Net-(C50-Pad1)") (class "Default")
      (node (ref "C50") (pin "1") (pinfunction "1_1") (pintype "passive"))
      (node (ref "R31") (pin "1") (pinfunction "1_1") (pintype "passive"))
      (node (ref "R32") (pin "2") (pinfunction "2_2") (pintype "passive"))
    )
    (net (code "31") (name "Net-(C52-Pad1)") (class "Default")
      (node (ref "C52") (pin "1") (pinfunction "1_1") (pintype "passive"))
      (node (ref "R33") (pin "1") (pinfunction "1_1") (pintype "passive"))
      (node (ref "R34") (pin "2") (pinfunction "2_2") (pintype "passive"))
    )
    (net (code "32") (name "Net-(H1-PadA)") (class "Default")
      (node (ref "H1") (pin "A") (pinfunction "A_A") (pintype "passive"))
      (node (ref "R16") (pin "1") (pinfunction "1_1") (pintype "passive"))
    )
    (net (code "33") (name "Net-(H2-PadA)") (class "Default")
      (node (ref "H2") (pin "A") (pinfunction "A_A") (pintype "passive"))
      (node (ref "R11") (pin "2") (pinfunction "2_2") (pintype "passive"))
    )
    (net (code "34") (name "Net-(R14-S)") (class "Default")
      (node (ref "C31") (pin "2") (pinfunction "2_2") (pintype "passive"))
      (node (ref "R14") (pin "2") (pinfunction "S_2") (pintype "passive"))
      (node (ref "U7") (pin "2") (pinfunction "FB_2") (pintype "passive"))
    )
    (net (code "35") (name "Net-(R22-Pad1)") (class "Default")
      (node (ref "R22") (pin "1") (pinfunction "1_1") (pintype "passive"))
      (node (ref "T2") (pin "B") (pinfunction "B_B") (pintype "passive"))
    )
    (net (code "36") (name "Net-(T5A-B)") (class "Default")
      (node (ref "R15") (pin "1") (pinfunction "1_1") (pintype "passive"))
      (node (ref "T5") (pin "8") (pinfunction "B_8") (pintype "passive"))
    )
    (net (code "37") (name "Net-(T5A-C1)") (class "Default")
      (node (ref "R35") (pin "2") (pinfunction "2_2") (pintype "passive"))
      (node (ref "R36") (pin "2") (pinfunction "2_2") (pintype "passive"))
      (node (ref "T5") (pin "1") (pinfunction "C1_1") (pintype "passive"))
      (node (ref "T5") (pin "2") (pinfunction "C2_2") (pintype "passive"))
    )
    (net (code "38") (name "Net-(T5B-B)") (class "Default")
      (node (ref "R35") (pin "1") (pinfunction "1_1") (pintype "passive"))
      (node (ref "T5") (pin "6") (pinfunction "B_6") (pintype "passive"))
    )
    (net (code "39") (name "Net-(T5B-C1)") (class "Default")
      (node (ref "T5") (pin "3") (pinfunction "C1_3") (pintype "passive"))
      (node (ref "T5") (pin "4") (pinfunction "C2_4") (pintype "passive"))
      (node (ref "X2") (pin "1") (pinfunction "P_1") (pintype "passive"))
    )
    (net (code "40") (name "Net-(U1A-OUTL)") (class "Default")
      (node (ref "R9") (pin "1") (pinfunction "1_1") (pintype "passive"))
      (node (ref "U1") (pin "6") (pinfunction "OUTL_6") (pintype "output"))
    )
    (net (code "41") (name "Net-(U1A-OUTR)") (class "Default")
      (node (ref "R10") (pin "1") (pinfunction "1_1") (pintype "passive"))
      (node (ref "U1") (pin "7") (pinfunction "OUTR_7") (pintype "output"))
    )
    (net (code "42") (name "Net-(U1B-CAPM)") (class "Default")
      (node (ref "C40") (pin "1") (pinfunction "1_1") (pintype "passive"))
      (node (ref "U1") (pin "4") (pinfunction "CAPM_4") (pintype "output"))
    )
    (net (code "43") (name "Net-(U1B-CAPP)") (class "Default")
      (node (ref "C40") (pin "2") (pinfunction "2_2") (pintype "passive"))
      (node (ref "U1") (pin "2") (pinfunction "CAPP_2") (pintype "output"))
    )
    (net (code "44") (name "Net-(U1B-LDOO)") (class "Default")
      (node (ref "C41") (pin "1") (pinfunction "1_1") (pintype "passive"))
      (node (ref "U1") (pin "18") (pinfunction "LDOO_18") (pintype "output"))
    )
    (net (code "45") (name "Net-(U1B-VNEG)") (class "Default")
      (node (ref "C11") (pin "1") (pinfunction "1_1") (pintype "passive"))
      (node (ref "U1") (pin "5") (pinfunction "VNEG_5") (pintype "output"))
    )
    (net (code "46") (name "Net-(U3-EN)") (class "Default")
      (node (ref "C8") (pin "1") (pinfunction "1_1") (pintype "passive"))
      (node (ref "R1") (pin "1") (pinfunction "1_1") (pintype "passive"))
      (node (ref "U3") (pin "8") (pinfunction "EN_8") (pintype "input"))
    )
    (net (code "47") (name "Net-(U3-LO)") (class "Default")
      (node (ref "C10") (pin "2") (pinfunction "2_2") (pintype "passive"))
      (node (ref "U3") (pin "6") (pinfunction "LO_6") (pintype "input"))
    )
    (net (code "48") (name "Net-(U3-RF)") (class "Default")
      (node (ref "C39") (pin "1") (pinfunction "1_1") (pintype "passive"))
      (node (ref "U3") (pin "11") (pinfunction "RF_11") (pintype "output"))
    )
    (net (code "49") (name "Net-(U3-VPS1)") (class "Default")
      (node (ref "C3") (pin "1") (pinfunction "1_1") (pintype "passive"))
      (node (ref "C4") (pin "1") (pinfunction "1_1") (pintype "passive"))
      (node (ref "FB3") (pin "1") (pinfunction "1_1") (pintype "passive"))
      (node (ref "U3") (pin "7") (pinfunction "VPS1_7") (pintype "power_in"))
    )
    (net (code "50") (name "Net-(U3-VPS2)") (class "Default")
      (node (ref "C5") (pin "1") (pinfunction "1_1") (pintype "passive"))
      (node (ref "C6") (pin "1") (pinfunction "1_1") (pintype "passive"))
      (node (ref "FB2") (pin "1") (pinfunction "1_1") (pintype "passive"))
      (node (ref "U3") (pin "12") (pinfunction "VPS2_12") (pintype "power_in"))
    )
    (net (code "51") (name "Net-(U3-~{LO})") (class "Default")
      (node (ref "C9") (pin "2") (pinfunction "2_2") (pintype "passive"))
      (node (ref "U3") (pin "5") (pinfunction "~{LO}_5") (pintype "input"))
    )
    (net (code "52") (name "Net-(U4-EN)") (class "Default")
      (node (ref "C12") (pin "1") (pinfunction "1_1") (pintype "passive"))
      (node (ref "C2") (pin "1") (pinfunction "1_1") (pintype "passive"))
      (node (ref "FB1") (pin "2") (pinfunction "2_2") (pintype "passive"))
      (node (ref "U4") (pin "1") (pinfunction "IN_1") (pintype "input"))
      (node (ref "U4") (pin "3") (pinfunction "EN_3") (pintype "input"))
    )
    (net (code "53") (name "Net-(U5B-EN)") (class "Default")
      (node (ref "T2") (pin "C") (pinfunction "C_C") (pintype "passive"))
      (node (ref "U5") (pin "4") (pinfunction "EN_4") (pintype "input"))
    )
    (net (code "54") (name "Net-(U5B-IN)") (class "Default")
      (node (ref "C22") (pin "2") (pinfunction "2_2") (pintype "passive"))
      (node (ref "U5") (pin "2") (pinfunction "IN_2") (pintype "input"))
    )
    (net (code "55") (name "Net-(U5B-OUT)") (class "Default")
      (node (ref "C23") (pin "1") (pinfunction "1_1") (pintype "passive"))
      (node (ref "L5") (pin "2") (pinfunction "2_2") (pintype "passive"))
      (node (ref "U5") (pin "7") (pinfunction "OUT_7") (pintype "output"))
    )
    (net (code "56") (name "Net-(U7-NR{slash}SS)") (class "Default")
      (node (ref "C29") (pin "1") (pinfunction "1_1") (pintype "passive"))
      (node (ref "U7") (pin "6") (pinfunction "NR/SS_6") (pintype "passive"))
    )
    (net (code "57") (name "Net-(U8A-+IN)") (class "Default")
      (node (ref "C49") (pin "1") (pinfunction "1_1") (pintype "passive"))
      (node (ref "R32") (pin "1") (pinfunction "1_1") (pintype "passive"))
      (node (ref "U8") (pin "3") (pinfunction "+IN_3") (pintype "input"))
    )
    (net (code "58") (name "Net-(U8A--IN)") (class "Default")
      (node (ref "C50") (pin "2") (pinfunction "2_2") (pintype "passive"))
      (node (ref "R33") (pin "2") (pinfunction "2_2") (pintype "passive"))
      (node (ref "U8") (pin "1") (pinfunction "OUT_1") (pintype "output"))
      (node (ref "U8") (pin "2") (pinfunction "-IN_2") (pintype "input"))
    )
    (net (code "59") (name "Net-(U8B-+IN)") (class "Default")
      (node (ref "C13") (pin "1") (pinfunction "1_1") (pintype "passive"))
      (node (ref "C14") (pin "1") (pinfunction "1_1") (pintype "passive"))
      (node (ref "R3") (pin "1") (pinfunction "1_1") (pintype "passive"))
      (node (ref "R4") (pin "2") (pinfunction "2_2") (pintype "passive"))
      (node (ref "R5") (pin "1") (pinfunction "1_1") (pintype "passive"))
      (node (ref "R6") (pin "1") (pinfunction "1_1") (pintype "passive"))
      (node (ref "U8") (pin "5") (pinfunction "+IN_5") (pintype "input"))
      (node (ref "U9") (pin "5") (pinfunction "+IN_5") (pintype "input"))
    )
    (net (code "60") (name "Net-(U8B--IN)") (class "Default")
      (node (ref "R29") (pin "1") (pinfunction "1_1") (pintype "passive"))
      (node (ref "R30") (pin "1") (pinfunction "1_1") (pintype "passive"))
      (node (ref "U8") (pin "6") (pinfunction "-IN_6") (pintype "input"))
    )
    (net (code "61") (name "Net-(U8C-+IN)") (class "Default")
      (node (ref "C52") (pin "2") (pinfunction "2_2") (pintype "passive"))
      (node (ref "U8") (pin "10") (pinfunction "+IN_10") (pintype "input"))
      (node (ref "U8") (pin "13") (pinfunction "-IN_13") (pintype "input"))
      (node (ref "U8") (pin "14") (pinfunction "OUT_14") (pintype "output"))
    )
    (net (code "62") (name "Net-(U8D-+IN)") (class "Default")
      (node (ref "C51") (pin "1") (pinfunction "1_1") (pintype "passive"))
      (node (ref "R34") (pin "1") (pinfunction "1_1") (pintype "passive"))
      (node (ref "U8") (pin "12") (pinfunction "+IN_12") (pintype "input"))
    )
    (net (code "63") (name "Net-(U9A-+IN)") (class "Default")
      (node (ref "C44") (pin "1") (pinfunction "1_1") (pintype "passive"))
      (node (ref "R27") (pin "1") (pinfunction "1_1") (pintype "passive"))
      (node (ref "U9") (pin "3") (pinfunction "+IN_3") (pintype "input"))
    )
    (net (code "64") (name "Net-(U9A--IN)") (class "Default")
      (node (ref "C47") (pin "2") (pinfunction "2_2") (pintype "passive"))
      (node (ref "U9") (pin "1") (pinfunction "OUT_1") (pintype "output"))
      (node (ref "U9") (pin "10") (pinfunction "+IN_10") (pintype "input"))
      (node (ref "U9") (pin "2") (pinfunction "-IN_2") (pintype "input"))
    )
    (net (code "65") (name "Net-(U9B--IN)") (class "Default")
      (node (ref "R19") (pin "1") (pinfunction "1_1") (pintype "passive"))
      (node (ref "R23") (pin "1") (pinfunction "1_1") (pintype "passive"))
      (node (ref "U9") (pin "6") (pinfunction "-IN_6") (pintype "input"))
    )
    (net (code "66") (name "Net-(U9D-+IN)") (class "Default")
      (node (ref "C42") (pin "1") (pinfunction "1_1") (pintype "passive"))
      (node (ref "R25") (pin "1") (pinfunction "1_1") (pintype "passive"))
      (node (ref "U9") (pin "12") (pinfunction "+IN_12") (pintype "input"))
    )
    (net (code "67") (name "Net-(U9D--IN)") (class "Default")
      (node (ref "C43") (pin "2") (pinfunction "2_2") (pintype "passive"))
      (node (ref "R26") (pin "2") (pinfunction "2_2") (pintype "passive"))
      (node (ref "U9") (pin "13") (pinfunction "-IN_13") (pintype "input"))
      (node (ref "U9") (pin "14") (pinfunction "OUT_14") (pintype "output"))
    )
    (net (code "68") (name "Net-(X1-GPIO14,UART0_TXD)") (class "Default")
      (node (ref "X1") (pin "P1_8") (pinfunction "GPIO14,UART0_TXD_P1_8") (pintype "bidirectional"))
      (node (ref "X11") (pin "1") (pinfunction "P_1") (pintype "passive"))
    )
    (net (code "69") (name "Net-(X1-GPIO15,UART0_RXD)") (class "Default")
      (node (ref "X1") (pin "P1_10") (pinfunction "GPIO15,UART0_RXD_P1_10") (pintype "bidirectional"))
      (node (ref "X10") (pin "1") (pinfunction "P_1") (pintype "passive"))
    )
    (net (code "70") (name "Net-(X1-GPIO17)") (class "Default")
      (node (ref "X1") (pin "P1_11") (pinfunction "GPIO17_P1_11") (pintype "bidirectional"))
      (node (ref "X6") (pin "1") (pinfunction "P_1") (pintype "passive"))
    )
    (net (code "71") (name "Net-(X1-GPIO18)") (class "Default")
      (node (ref "R11") (pin "1") (pinfunction "1_1") (pintype "passive"))
      (node (ref "X1") (pin "P1_12") (pinfunction "GPIO18_P1_12") (pintype "bidirectional"))
    )
    (net (code "72") (name "Net-(X1-GPIO27)") (class "Default")
      (node (ref "R15") (pin "2") (pinfunction "2_2") (pintype "passive"))
      (node (ref "X1") (pin "P1_13") (pinfunction "GPIO27_P1_13") (pintype "bidirectional"))
    )
    (net (code "73") (name "Net-(X9-P)") (class "Default")
      (node (ref "U6") (pin "OUT") (pinfunction "OUT_OUT") (pintype "output"))
      (node (ref "X9") (pin "1") (pinfunction "P_1") (pintype "passive"))
    )
    (net (code "74") (name "PA_EN") (class "Default")
      (node (ref "R13") (pin "1") (pinfunction "1_1") (pintype "passive"))
      (node (ref "U7") (pin "5") (pinfunction "EN_5") (pintype "input"))
      (node (ref "X1") (pin "P1_15") (pinfunction "GPIO22_P1_15") (pintype "bidirectional"))
    )
    (net (code "75") (name "PCM_CLK") (class "Default")
      (node (ref "U1") (pin "13") (pinfunction "BCK_13") (pintype "input"))
      (node (ref "X1") (pin "P5_3") (pinfunction "GPIO28_P5_3") (pintype "bidirectional"))
    )
    (net (code "76") (name "PCM_DOUT") (class "Default")
      (node (ref "U1") (pin "14") (pinfunction "DIN_14") (pintype "input"))
      (node (ref "X1") (pin "P5_6") (pinfunction "GPIO31_P5_6") (pintype "bidirectional"))
    )
    (net (code "77") (name "PCM_FS") (class "Default")
      (node (ref "U1") (pin "15") (pinfunction "LRCLK_15") (pintype "input"))
      (node (ref "X1") (pin "P5_4") (pinfunction "GPIO29_P5_4") (pintype "bidirectional"))
    )
    (net (code "78") (name "PRE_EN") (class "Default")
      (node (ref "R21") (pin "1") (pinfunction "1_1") (pintype "passive"))
      (node (ref "R22") (pin "2") (pinfunction "2_2") (pintype "passive"))
      (node (ref "X1") (pin "P1_23") (pinfunction "GPIO11_SCLK_P1_23") (pintype "bidirectional"))
    )
    (net (code "79") (name "SCL") (class "Default")
      (node (ref "U2") (pin "6") (pinfunction "SCL_6") (pintype "input"))
      (node (ref "X1") (pin "P1_5") (pinfunction "GPIO3,I2C0_SCL_P1_5") (pintype "bidirectional"))
      (node (ref "X5") (pin "1") (pinfunction "P_1") (pintype "passive"))
    )
    (net (code "80") (name "SDA") (class "Default")
      (node (ref "U2") (pin "7") (pinfunction "SDA_7") (pintype "bidirectional"))
      (node (ref "X1") (pin "P1_3") (pinfunction "GPIO2,I2C0_SDA_P1_3") (pintype "bidirectional"))
      (node (ref "X4") (pin "1") (pinfunction "P_1") (pintype "passive"))
    )
    (net (code "81") (name "VGG") (class "Default")
      (node (ref "C28") (pin "1") (pinfunction "1_1") (pintype "passive"))
      (node (ref "C31") (pin "1") (pinfunction "1_1") (pintype "passive"))
      (node (ref "C34") (pin "1") (pinfunction "1_1") (pintype "passive"))
      (node (ref "FB4") (pin "1") (pinfunction "1_1") (pintype "passive"))
      (node (ref "R14") (pin "1") (pinfunction "A_1") (pintype "passive"))
      (node (ref "U7") (pin "1") (pinfunction "OUT_1") (pintype "power_in"))
    )
    (net (code "82") (name "unconnected-(U2-EOC-Pad2)") (class "Default")
      (node (ref "U2") (pin "2") (pinfunction "EOC_2") (pintype "output"))
    )
    (net (code "83") (name "unconnected-(U2-NC-Pad5)") (class "Default")
      (node (ref "U2") (pin "5") (pinfunction "NC_5") (pintype "bidirectional"))
    )
    (net (code "84") (name "unconnected-(U2-XCLR-Pad8)") (class "Default")
      (node (ref "U2") (pin "8") (pinfunction "XCLR_8") (pintype "input"))
    )
    (net (code "85") (name "unconnected-(U4-BYP-Pad4)") (class "Default")
      (node (ref "U4") (pin "4") (pinfunction "BYP_4") (pintype "passive"))
    )
    (net (code "86") (name "unconnected-(U7-DNC-Pad7)") (class "Default")
      (node (ref "U7") (pin "7") (pinfunction "DNC_7") (pintype "no_connect"))
    )
    (net (code "87") (name "unconnected-(U7-NC-Pad3)") (class "Default")
      (node (ref "U7") (pin "3") (pinfunction "NC_3") (pintype "no_connect"))
    )
    (net (code "88") (name "unconnected-(X1-GPIO7,SPI0_CE1-PadP1_26)") (class "Default")
      (node (ref "X1") (pin "P1_26") (pinfunction "GPIO7,SPI0_CE1_P1_26") (pintype "bidirectional"))
    )
    (net (code "89") (name "unconnected-(X1-GPIO8,SPI0_CE0-PadP1_24)") (class "Default")
      (node (ref "X1") (pin "P1_24") (pinfunction "GPIO8,SPI0_CE0_P1_24") (pintype "bidirectional"))
    )
    (net (code "90") (name "unconnected-(X1-GPIO10_MOSI-PadP1_19)") (class "Default")
      (node (ref "X1") (pin "P1_19") (pinfunction "GPIO10_MOSI_P1_19") (pintype "bidirectional"))
    )
    (net (code "91") (name "unconnected-(X1-GPIO23-PadP1_16)") (class "Default")
      (node (ref "X1") (pin "P1_16") (pinfunction "GPIO23_P1_16") (pintype "bidirectional"))
    )
    (net (code "92") (name "unconnected-(X1-GPIO24-PadP1_18)") (class "Default")
      (node (ref "X1") (pin "P1_18") (pinfunction "GPIO24_P1_18") (pintype "bidirectional"))
    )
    (net (code "93") (name "unconnected-(X1-GPIO25-PadP1_22)") (class "Default")
      (node (ref "X1") (pin "P1_22") (pinfunction "GPIO25_P1_22") (pintype "bidirectional"))
    )
    (net (code "94") (name "unconnected-(X1-GPIO30-PadP5_5)") (class "Default")
      (node (ref "X1") (pin "P5_5") (pinfunction "GPIO30_P5_5") (pintype "bidirectional"))
    )
  )
)
